# untitled.net
KiCad netlist of a schematic drawn in EAGLE
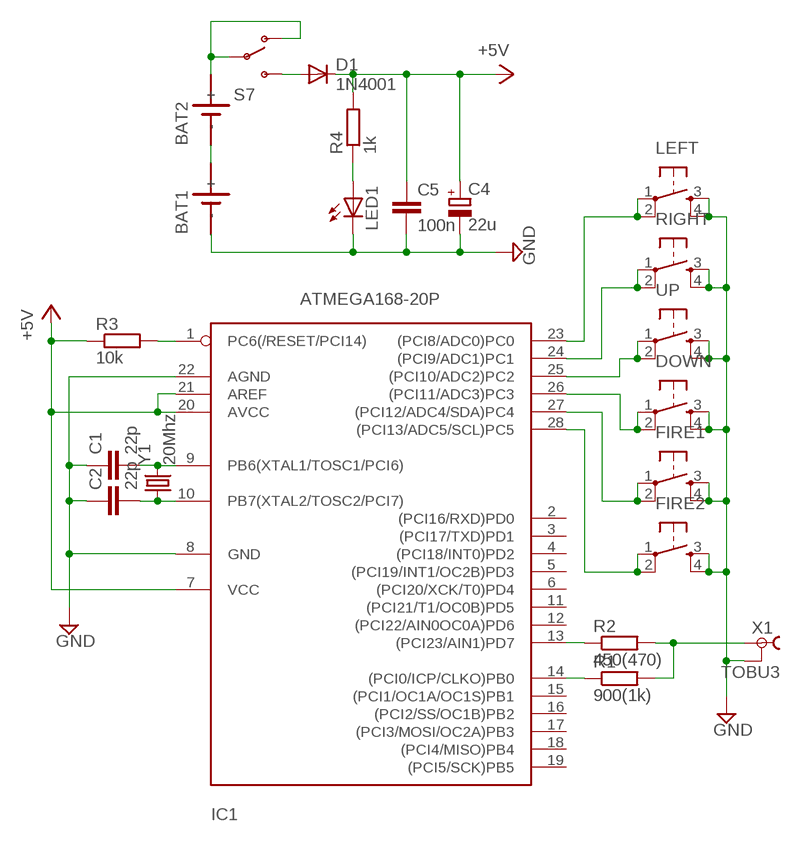
[diagram p0: schematic, sheet 1]

(export (version "E")
  (design (tool "Eeschema 10.0.6"))
  (components
    (comp (ref "BAT1")
      (value "SN2032")
      (footprint "eagle-import:SN2032")
      (libsource (lib "eagle-import") (part "SN2032"))
    )
    (comp (ref "BAT2")
      (value "SN2032")
      (footprint "eagle-import:SN2032")
      (libsource (lib "eagle-import") (part "SN2032"))
    )
    (comp (ref "C1")
      (value "22p")
      (footprint "eagle-import:C025-025X050")
      (libsource (lib "eagle-import") (part "C-EU025-025X050"))
    )
    (comp (ref "C2")
      (value "22p")
      (footprint "eagle-import:C025-025X050")
      (libsource (lib "eagle-import") (part "C-EU025-025X050"))
    )
    (comp (ref "C4")
      (value "22u")
      (footprint "eagle-import:TT2D5L")
      (libsource (lib "eagle-import") (part "CPOL-EUTT2D5L"))
    )
    (comp (ref "C5")
      (value "100n")
      (footprint "eagle-import:C025-025X050")
      (libsource (lib "eagle-import") (part "C-EU025-025X050"))
    )
    (comp (ref "D1")
      (value "1N4001")
      (footprint "eagle-import:D-2.5")
      (libsource (lib "eagle-import") (part "DIODE-D-2.5"))
    )
    (comp (ref "DOWN")
      (value "TAC_SWITCHPTH")
      (footprint "eagle-import:TACTILE-PTH")
      (libsource (lib "eagle-import") (part "TAC_SWITCHPTH"))
    )
    (comp (ref "FIRE1")
      (value "TAC_SWITCHPTH")
      (footprint "eagle-import:TACTILE-PTH")
      (libsource (lib "eagle-import") (part "TAC_SWITCHPTH"))
    )
    (comp (ref "FIRE2")
      (value "TAC_SWITCHPTH")
      (footprint "eagle-import:TACTILE-PTH")
      (libsource (lib "eagle-import") (part "TAC_SWITCHPTH"))
    )
    (comp (ref "IC1")
      (value "ATMEGA168-20P")
      (footprint "eagle-import:DIL28-3")
      (libsource (lib "eagle-import") (part "ATMEGA168P-20"))
    )
    (comp (ref "LED1")
      (value "LED3MM")
      (footprint "eagle-import:LED3MM")
      (libsource (lib "eagle-import") (part "LED3MM"))
    )
    (comp (ref "LEFT")
      (value "TAC_SWITCHPTH")
      (footprint "eagle-import:TACTILE-PTH")
      (libsource (lib "eagle-import") (part "TAC_SWITCHPTH"))
    )
    (comp (ref "R1")
      (value "900(1k)")
      (footprint "eagle-import:0207_2V")
      (libsource (lib "eagle-import") (part "R-EU_0207/2V"))
    )
    (comp (ref "R2")
      (value "450(470)")
      (footprint "eagle-import:0207_2V")
      (libsource (lib "eagle-import") (part "R-EU_0207/2V"))
    )
    (comp (ref "R3")
      (value "10k")
      (footprint "eagle-import:0207_10")
      (libsource (lib "eagle-import") (part "R-EU_0207/10"))
    )
    (comp (ref "R4")
      (value "1k")
      (footprint "eagle-import:0204V")
      (libsource (lib "eagle-import") (part "R-EU_0204/2V"))
    )
    (comp (ref "RIGHT")
      (value "TAC_SWITCHPTH")
      (footprint "eagle-import:TACTILE-PTH")
      (libsource (lib "eagle-import") (part "TAC_SWITCHPTH"))
    )
    (comp (ref "S7")
      (value "SWITCH-SPSTPTH")
      (footprint "eagle-import:SWITCH-SPDT")
      (libsource (lib "eagle-import") (part "SWITCH-SPSTPTH"))
    )
    (comp (ref "UP")
      (value "TAC_SWITCHPTH")
      (footprint "eagle-import:TACTILE-PTH")
      (libsource (lib "eagle-import") (part "TAC_SWITCHPTH"))
    )
    (comp (ref "X1")
      (value "TOBU3")
      (footprint "eagle-import:TOBU3")
      (fields (field (name "MF") "FARNELL") (field (name "MPN") "TOBU 3"))
      (libsource (lib "eagle-import") (part "TOBU3"))
    )
    (comp (ref "Y1")
      (value "20Mhz")
      (footprint "eagle-import:HC49US")
      (libsource (lib "eagle-import") (part "CRYSTALHC49US"))
    )
  )
  (nets
    (net (code "1") (name "+5V") (class "Default")
      (node (ref "C4") (pin "+") (pinfunction "+_+") (pintype "passive"))
      (node (ref "C5") (pin "1") (pinfunction "1_1") (pintype "passive"))
      (node (ref "D1") (pin "C") (pinfunction "C_C") (pintype "passive"))
      (node (ref "IC1") (pin "20") (pinfunction "AVCC_20") (pintype "bidirectional"))
      (node (ref "IC1") (pin "21") (pinfunction "AREF_21") (pintype "bidirectional"))
      (node (ref "IC1") (pin "7") (pinfunction "VCC_7") (pintype "bidirectional"))
      (node (ref "R3") (pin "1") (pinfunction "1_1") (pintype "passive"))
      (node (ref "R4") (pin "2") (pinfunction "2_2") (pintype "passive"))
    )
    (net (code "2") (name "GND") (class "Default")
      (node (ref "BAT1") (pin "-") (pinfunction "-_-") (pintype "passive"))
      (node (ref "C1") (pin "1") (pinfunction "1_1") (pintype "passive"))
      (node (ref "C2") (pin "1") (pinfunction "1_1") (pintype "passive"))
      (node (ref "C4") (pin "-") (pinfunction "-_-") (pintype "passive"))
      (node (ref "C5") (pin "2") (pinfunction "2_2") (pintype "passive"))
      (node (ref "DOWN") (pin "3") (pinfunction "3_3") (pintype "passive"))
      (node (ref "DOWN") (pin "4") (pinfunction "4_4") (pintype "passive"))
      (node (ref "FIRE1") (pin "3") (pinfunction "3_3") (pintype "passive"))
      (node (ref "FIRE1") (pin "4") (pinfunction "4_4") (pintype "passive"))
      (node (ref "FIRE2") (pin "3") (pinfunction "3_3") (pintype "passive"))
      (node (ref "FIRE2") (pin "4") (pinfunction "4_4") (pintype "passive"))
      (node (ref "IC1") (pin "22") (pinfunction "AGND_22") (pintype "bidirectional"))
      (node (ref "IC1") (pin "8") (pinfunction "GND_8") (pintype "bidirectional"))
      (node (ref "LED1") (pin "K") (pinfunction "C_K") (pintype "passive"))
      (node (ref "LEFT") (pin "3") (pinfunction "3_3") (pintype "passive"))
      (node (ref "LEFT") (pin "4") (pinfunction "4_4") (pintype "passive"))
      (node (ref "RIGHT") (pin "3") (pinfunction "3_3") (pintype "passive"))
      (node (ref "RIGHT") (pin "4") (pinfunction "4_4") (pintype "passive"))
      (node (ref "UP") (pin "3") (pinfunction "3_3") (pintype "passive"))
      (node (ref "UP") (pin "4") (pinfunction "4_4") (pintype "passive"))
      (node (ref "X1") (pin "2") (pinfunction "2_2") (pintype "passive"))
      (node (ref "X1") (pin "2@1") (pinfunction "2_2@1") (pintype "passive"))
      (node (ref "X1") (pin "2@2") (pinfunction "2_2@2") (pintype "passive"))
    )
    (net (code "3") (name "Net-(BAT1-Pad+)") (class "Default")
      (node (ref "BAT1") (pin "+") (pinfunction "+_+") (pintype "passive"))
      (node (ref "BAT2") (pin "-") (pinfunction "-_-") (pintype "passive"))
    )
    (net (code "4") (name "Net-(IC1-(PCI0{slash}ICP{slash}CLKO)PB0)") (class "Default")
      (node (ref "IC1") (pin "14") (pinfunction "(PCI0/ICP/CLKO)PB0_14") (pintype "bidirectional"))
      (node (ref "R1") (pin "1") (pinfunction "1_1") (pintype "passive"))
    )
    (net (code "5") (name "Net-(IC1-(PCI8{slash}ADC0)PC0)") (class "Default")
      (node (ref "IC1") (pin "23") (pinfunction "(PCI8/ADC0)PC0_23") (pintype "bidirectional"))
      (node (ref "LEFT") (pin "1") (pinfunction "1_1") (pintype "passive"))
      (node (ref "LEFT") (pin "2") (pinfunction "2_2") (pintype "passive"))
    )
    (net (code "6") (name "Net-(IC1-(PCI9{slash}ADC1)PC1)") (class "Default")
      (node (ref "IC1") (pin "24") (pinfunction "(PCI9/ADC1)PC1_24") (pintype "bidirectional"))
      (node (ref "RIGHT") (pin "1") (pinfunction "1_1") (pintype "passive"))
      (node (ref "RIGHT") (pin "2") (pinfunction "2_2") (pintype "passive"))
    )
    (net (code "7") (name "Net-(IC1-(PCI10{slash}ADC2)PC2)") (class "Default")
      (node (ref "IC1") (pin "25") (pinfunction "(PCI10/ADC2)PC2_25") (pintype "bidirectional"))
      (node (ref "UP") (pin "1") (pinfunction "1_1") (pintype "passive"))
      (node (ref "UP") (pin "2") (pinfunction "2_2") (pintype "passive"))
    )
    (net (code "8") (name "Net-(IC1-(PCI11{slash}ADC3)PC3)") (class "Default")
      (node (ref "DOWN") (pin "1") (pinfunction "1_1") (pintype "passive"))
      (node (ref "DOWN") (pin "2") (pinfunction "2_2") (pintype "passive"))
      (node (ref "IC1") (pin "26") (pinfunction "(PCI11/ADC3)PC3_26") (pintype "bidirectional"))
    )
    (net (code "9") (name "Net-(IC1-(PCI12{slash}ADC4{slash}SDA)PC4)") (class "Default")
      (node (ref "FIRE1") (pin "1") (pinfunction "1_1") (pintype "passive"))
      (node (ref "FIRE1") (pin "2") (pinfunction "2_2") (pintype "passive"))
      (node (ref "IC1") (pin "27") (pinfunction "(PCI12/ADC4/SDA)PC4_27") (pintype "bidirectional"))
    )
    (net (code "10") (name "Net-(IC1-(PCI13{slash}ADC5{slash}SCL)PC5)") (class "Default")
      (node (ref "FIRE2") (pin "1") (pinfunction "1_1") (pintype "passive"))
      (node (ref "FIRE2") (pin "2") (pinfunction "2_2") (pintype "passive"))
      (node (ref "IC1") (pin "28") (pinfunction "(PCI13/ADC5/SCL)PC5_28") (pintype "bidirectional"))
    )
    (net (code "11") (name "Net-(IC1-(PCI23{slash}AIN1)PD7)") (class "Default")
      (node (ref "IC1") (pin "13") (pinfunction "(PCI23/AIN1)PD7_13") (pintype "bidirectional"))
      (node (ref "R2") (pin "1") (pinfunction "1_1") (pintype "passive"))
    )
    (net (code "12") (name "Net-(IC1-PB6(XTAL1{slash}TOSC1{slash}PCI6))") (class "Default")
      (node (ref "C1") (pin "2") (pinfunction "2_2") (pintype "passive"))
      (node (ref "IC1") (pin "9") (pinfunction "PB6(XTAL1/TOSC1/PCI6)_9") (pintype "bidirectional"))
      (node (ref "Y1") (pin "2") (pinfunction "2_2") (pintype "passive"))
    )
    (net (code "13") (name "Net-(IC1-PB7(XTAL2{slash}TOSC2{slash}PCI7))") (class "Default")
      (node (ref "C2") (pin "2") (pinfunction "2_2") (pintype "passive"))
      (node (ref "IC1") (pin "10") (pinfunction "PB7(XTAL2/TOSC2/PCI7)_10") (pintype "bidirectional"))
      (node (ref "Y1") (pin "1") (pinfunction "1_1") (pintype "passive"))
    )
    (net (code "14") (name "Net-(IC1-PC6({slash}RESET{slash}PCI14))") (class "Default")
      (node (ref "IC1") (pin "1") (pinfunction "PC6(/RESET/PCI14)_1") (pintype "bidirectional"))
      (node (ref "R3") (pin "2") (pinfunction "2_2") (pintype "passive"))
    )
    (net (code "15") (name "Net-(LED1-PadA)") (class "Default")
      (node (ref "LED1") (pin "A") (pinfunction "A_A") (pintype "passive"))
      (node (ref "R4") (pin "1") (pinfunction "1_1") (pintype "passive"))
    )
    (net (code "16") (name "Net-(R1-Pad2)") (class "Default")
      (node (ref "R1") (pin "2") (pinfunction "2_2") (pintype "passive"))
      (node (ref "R2") (pin "2") (pinfunction "2_2") (pintype "passive"))
      (node (ref "X1") (pin "1") (pinfunction "1_1") (pintype "passive"))
    )
    (net (code "17") (name "Net-(S7-O)") (class "Default")
      (node (ref "BAT2") (pin "+") (pinfunction "+_+") (pintype "passive"))
      (node (ref "S7") (pin "1") (pinfunction "O_1") (pintype "passive"))
      (node (ref "S7") (pin "2") (pinfunction "P_2") (pintype "passive"))
    )
    (net (code "18") (name "Net-(S7-S)") (class "Default")
      (node (ref "D1") (pin "A") (pinfunction "A_A") (pintype "passive"))
      (node (ref "S7") (pin "3") (pinfunction "S_3") (pintype "passive"))
    )
    (net (code "19") (name "unconnected-(IC1-(PCI1{slash}OC1A{slash}OC1S)PB1-Pad15)") (class "Default")
      (node (ref "IC1") (pin "15") (pinfunction "(PCI1/OC1A/OC1S)PB1_15") (pintype "bidirectional"))
    )
    (net (code "20") (name "unconnected-(IC1-(PCI2{slash}SS{slash}OC1B)PB2-Pad16)") (class "Default")
      (node (ref "IC1") (pin "16") (pinfunction "(PCI2/SS/OC1B)PB2_16") (pintype "bidirectional"))
    )
    (net (code "21") (name "unconnected-(IC1-(PCI3{slash}MOSI{slash}OC2A)PB3-Pad17)") (class "Default")
      (node (ref "IC1") (pin "17") (pinfunction "(PCI3/MOSI/OC2A)PB3_17") (pintype "bidirectional"))
    )
    (net (code "22") (name "unconnected-(IC1-(PCI4{slash}MISO)PB4-Pad18)") (class "Default")
      (node (ref "IC1") (pin "18") (pinfunction "(PCI4/MISO)PB4_18") (pintype "bidirectional"))
    )
    (net (code "23") (name "unconnected-(IC1-(PCI5{slash}SCK)PB5-Pad19)") (class "Default")
      (node (ref "IC1") (pin "19") (pinfunction "(PCI5/SCK)PB5_19") (pintype "bidirectional"))
    )
    (net (code "24") (name "unconnected-(IC1-(PCI16{slash}RXD)PD0-Pad2)") (class "Default")
      (node (ref "IC1") (pin "2") (pinfunction "(PCI16/RXD)PD0_2") (pintype "bidirectional"))
    )
    (net (code "25") (name "unconnected-(IC1-(PCI17{slash}TXD)PD1-Pad3)") (class "Default")
      (node (ref "IC1") (pin "3") (pinfunction "(PCI17/TXD)PD1_3") (pintype "bidirectional"))
    )
    (net (code "26") (name "unconnected-(IC1-(PCI18{slash}INT0)PD2-Pad4)") (class "Default")
      (node (ref "IC1") (pin "4") (pinfunction "(PCI18/INT0)PD2_4") (pintype "bidirectional"))
    )
    (net (code "27") (name "unconnected-(IC1-(PCI19{slash}INT1{slash}OC2B)PD3-Pad5)") (class "Default")
      (node (ref "IC1") (pin "5") (pinfunction "(PCI19/INT1/OC2B)PD3_5") (pintype "bidirectional"))
    )
    (net (code "28") (name "unconnected-(IC1-(PCI20{slash}XCK{slash}T0)PD4-Pad6)") (class "Default")
      (node (ref "IC1") (pin "6") (pinfunction "(PCI20/XCK/T0)PD4_6") (pintype "bidirectional"))
    )
    (net (code "29") (name "unconnected-(IC1-(PCI21{slash}T1{slash}OC0B)PD5-Pad11)") (class "Default")
      (node (ref "IC1") (pin "11") (pinfunction "(PCI21/T1/OC0B)PD5_11") (pintype "bidirectional"))
    )
    (net (code "30") (name "unconnected-(IC1-(PCI22{slash}AIN0OC0A)PD6-Pad12)") (class "Default")
      (node (ref "IC1") (pin "12") (pinfunction "(PCI22/AIN0OC0A)PD6_12") (pintype "bidirectional"))
    )
  )
)
